# 2-FET_Control.net
KiCad netlist of a schematic drawn in Altium Designer
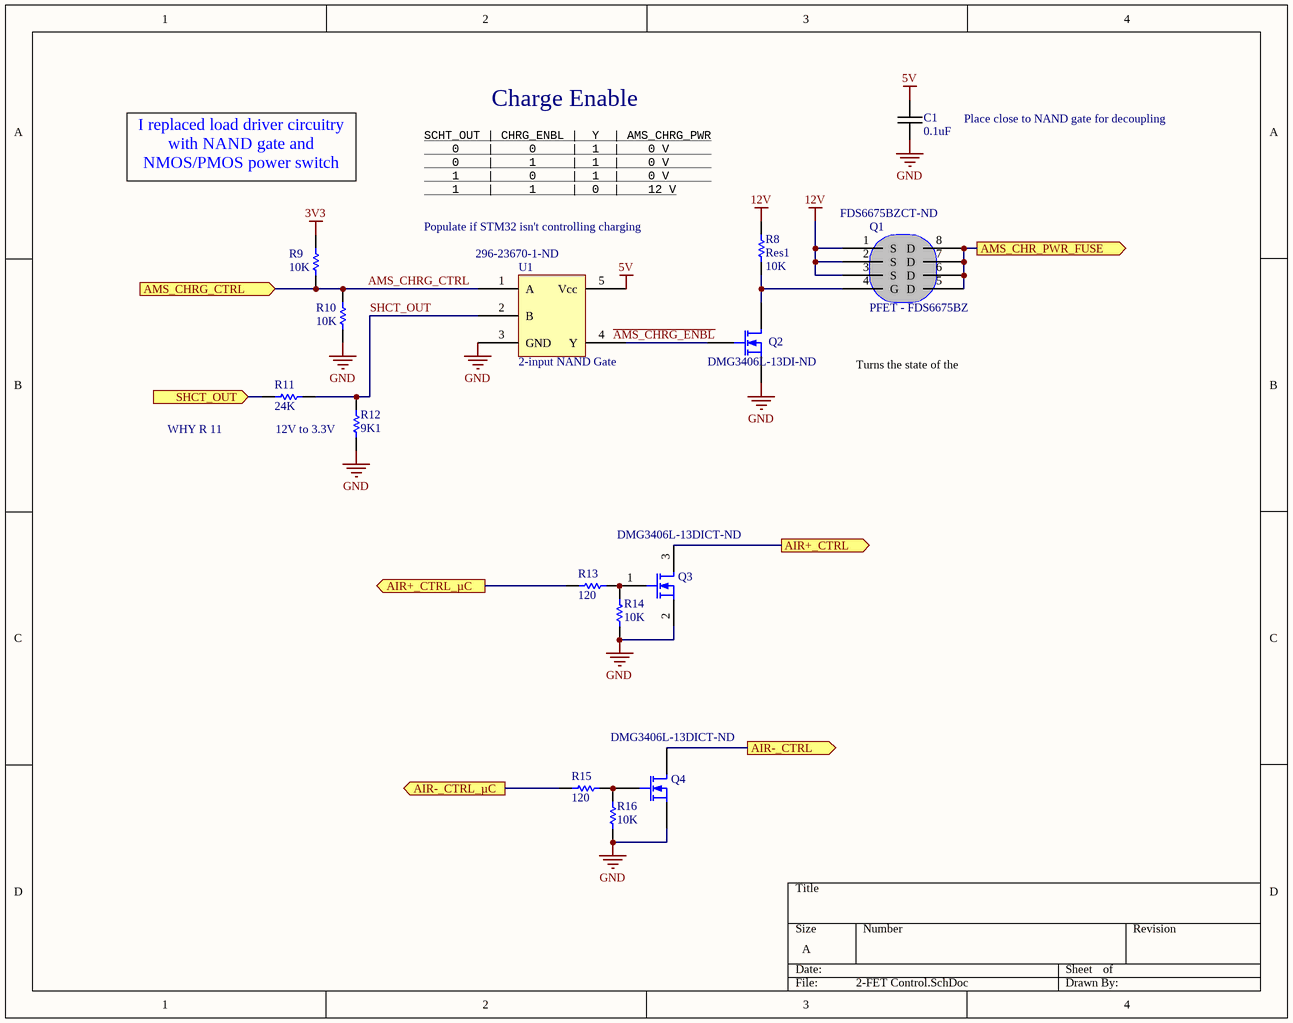
[diagram p0: 2-FET Control.SchDoc]

(export (version "E")
  (design (tool "Eeschema 10.0.6"))
  (components
    (comp (ref "C1")
      (value "0.1uF")
      (footprint "1608[0603]")
      (description "CAP CER 0.1UF 50V X7R 0603")
      (fields
        (field (name "MANUFACTURER") "Kemet")
        (field (name "MANUFACTURER PART NUMBER") "C0603C104K5RACAUTO")
      )
      (libsource (lib "vh_altium_library") (part "0805C-100nF-25V-X7R-MUR"))
    )
    (comp (ref "Q1")
      (value "PFET - FDS6675BZ")
      (footprint "SOIC127P600X175-8N")
      (description "MOSFET P-CH 8-SOIC")
      (fields
        (field (name "MANUFACTURER") "Fairchild/ON Semiconductor")
        (field (name "MANUFACTURER PART NUMBER") "FDS6675BZ")
        (field (name "SUPPLIER PART NUMBER 1") "FDS6675BZCT-ND")
      )
      (libsource (lib "Latching_Reset_Library") (part "MOSFET"))
    )
    (comp (ref "Q2")
      (value "~")
      (footprint "SOT-23_N")
      (description "N-Channel MOSFET")
      (fields
        (field (name "MANUFACTURER") "Infineon Technologies")
        (field (name "MANUFACTURER PART NUMBER") "IPD075N03L G")
        (field (name "SUPPLIER PART NUMBER 1") "DMG3406L-13DI-ND")
        (field (name "PUBLISHER") "Altium Limited")
      )
      (libsource (lib "") (part "MOSFET-N_1"))
    )
    (comp (ref "Q3")
      (value "~")
      (footprint "SOT-23_N")
      (description "N-Channel MOSFET")
      (fields
        (field (name "MANUFACTURER") "Infineon Technologies")
        (field (name "MANUFACTURER PART NUMBER") "IPD075N03L G")
        (field (name "SUPPLIER PART NUMBER 1") "DMG3406L-13DICT-ND")
        (field (name "PUBLISHER") "Altium Limited")
      )
      (libsource (lib "Miscellaneous Devices") (part "MOSFET-N"))
    )
    (comp (ref "Q4")
      (value "~")
      (footprint "SOT-23_N")
      (description "N-Channel MOSFET")
      (fields
        (field (name "MANUFACTURER") "Infineon Technologies")
        (field (name "MANUFACTURER PART NUMBER") "IPD075N03L G")
        (field (name "SUPPLIER PART NUMBER 1") "DMG3406L-13DICT-ND")
        (field (name "PUBLISHER") "Altium Limited")
      )
      (libsource (lib "") (part "MOSFET-N_1"))
    )
    (comp (ref "R8")
      (value "Res1")
      (footprint "1608[0603]")
      (description "RES SMD 10K OHM 5% 1/4W 0603")
      (fields
        (field (name "ALTIUM_VALUE") "10K")
        (field (name "MANUFACTURER") "Rohm Semiconductor")
        (field (name "MANUFACTURER PART NUMBER") "ESR03EZPJ103")
        (field (name "PUBLISHER") "Altium Limited")
      )
      (libsource (lib "Miscellaneous Devices") (part "Res1"))
    )
    (comp (ref "R9")
      (value "10K")
      (footprint "RESC0603(1608)_L")
      (description "0603 (1608 Metric) Chip Resistor")
      (libsource (lib "Altium Content Vault") (part "CMP-1591-00001-1"))
    )
    (comp (ref "R10")
      (value "10K")
      (footprint "RESC0603(1608)_L")
      (description "0603 (1608 Metric) Chip Resistor")
      (libsource (lib "Altium Content Vault") (part "CMP-1591-00001-1"))
    )
    (comp (ref "R11")
      (value "24K")
      (footprint "RESC0603(1608)_N")
      (description "24K 0.1W 5% 0603 (1608 Metric)  SMD")
      (fields (field (name "TOLERANCE") "5 %") (field (name "POWER") "0.1 W"))
      (libsource (lib "Altium Content Vault") (part "RES"))
    )
    (comp (ref "R12")
      (value "9K1")
      (footprint "RESC0603(1608)_M")
      (description "9K1 0.1W 5% 0603 (1608 Metric)  SMD")
      (fields (field (name "POWER") "0.1 W") (field (name "TOLERANCE") "5 %"))
      (libsource (lib "Altium Content Vault") (part "RES"))
    )
    (comp (ref "R13")
      (value "120")
      (footprint "1608[0603]")
      (description "Resistor")
      (fields
        (field (name "MANUFACTURER") "Panasonic Electronic Components")
        (field (name "MANUFACTURER PART NUMBER") "ERJ-3EKF60R4V")
        (field (name "PUBLISHER") "Altium Limited")
      )
      (libsource (lib "Miscellaneous Devices") (part "Res1"))
    )
    (comp (ref "R14")
      (value "10K")
      (footprint "1608[0603]")
      (description "Resistor")
      (fields
        (field (name "MANUFACTURER") "Rohm Semiconductor")
        (field (name "MANUFACTURER PART NUMBER") "ESR03EZPJ103")
        (field (name "PUBLISHER") "Altium Limited")
      )
      (libsource (lib "Miscellaneous Devices") (part "Res1"))
    )
    (comp (ref "R15")
      (value "120")
      (footprint "1608[0603]")
      (description "Resistor")
      (fields
        (field (name "MANUFACTURER") "Panasonic Electronic Components")
        (field (name "MANUFACTURER PART NUMBER") "ERJ-3EKF60R4V")
        (field (name "PUBLISHER") "Altium Limited")
      )
      (libsource (lib "Miscellaneous Devices") (part "Res1"))
    )
    (comp (ref "R16")
      (value "10K")
      (footprint "1608[0603]")
      (description "Resistor")
      (fields
        (field (name "MANUFACTURER") "Rohm Semiconductor")
        (field (name "MANUFACTURER PART NUMBER") "ESR03EZPJ103")
        (field (name "PUBLISHER") "Altium Limited")
      )
      (libsource (lib "Miscellaneous Devices") (part "Res1"))
    )
    (comp (ref "U1")
      (value "2-input NAND Gate")
      (footprint "SOT23-6_M")
      (description "IC GATE NAND 1CH 2-INP SC-70-5")
      (fields
        (field (name "MANUFACTURER") "Texas Instruments")
        (field (name "MANUFACTURER PART NUMBER") "SN74AHC1G00QDCKRQ1")
        (field (name "SUPPLIER PART NUMBER 1") "296-23670-1-ND")
      )
      (libsource (lib "FE Schem Lib") (part "NC7SZ08"))
    )
  )
  (nets
    (net (code "1") (name "/AIR+_CTRL") (class "Default")
      (node (ref "Q3") (pin "3") (pinfunction "D_3") (pintype "passive"))
    )
    (net (code "2") (name "/AIR+_CTRL_µC") (class "Default")
      (node (ref "R13") (pin "1") (pinfunction "1_1") (pintype "passive"))
    )
    (net (code "3") (name "/AIR-_CTRL") (class "Default")
      (node (ref "Q4") (pin "3") (pinfunction "D_3") (pintype "passive"))
    )
    (net (code "4") (name "/AIR-_CTRL_µC") (class "Default")
      (node (ref "R15") (pin "1") (pinfunction "1_1") (pintype "passive"))
    )
    (net (code "5") (name "/AMS_CHRG_CTRL") (class "Default")
      (node (ref "R10") (pin "2") (pinfunction "2_2") (pintype "passive"))
      (node (ref "R9") (pin "1") (pinfunction "1_1") (pintype "passive"))
      (node (ref "U1") (pin "1") (pinfunction "A_1") (pintype "passive"))
    )
    (net (code "6") (name "/AMS_CHR_PWR_FUSE") (class "Default")
      (node (ref "Q1") (pin "5") (pinfunction "D_5") (pintype "passive"))
      (node (ref "Q1") (pin "6") (pinfunction "D_6") (pintype "passive"))
      (node (ref "Q1") (pin "7") (pinfunction "D_7") (pintype "passive"))
      (node (ref "Q1") (pin "8") (pinfunction "D_8") (pintype "passive"))
    )
    (net (code "7") (name "/SHCT_OUT") (class "Default")
      (node (ref "R11") (pin "1") (pinfunction "1_1") (pintype "passive"))
      (node (ref "R11") (pin "2") (pinfunction "2_2") (pintype "passive"))
      (node (ref "R12") (pin "2") (pinfunction "2_2") (pintype "passive"))
      (node (ref "U1") (pin "2") (pinfunction "B_2") (pintype "passive"))
    )
    (net (code "9") (name "3V3") (class "Default")
      (node (ref "R9") (pin "2") (pinfunction "2_2") (pintype "passive"))
    )
    (net (code "10") (name "5V") (class "Default")
      (node (ref "C1") (pin "1") (pintype "passive"))
      (node (ref "U1") (pin "5") (pinfunction "Vcc_5") (pintype "passive"))
    )
    (net (code "11") (name "12V") (class "Default")
      (node (ref "Q1") (pin "1") (pinfunction "S_1") (pintype "passive"))
      (node (ref "Q1") (pin "2") (pinfunction "S_2") (pintype "passive"))
      (node (ref "Q1") (pin "3") (pinfunction "S_3") (pintype "passive"))
      (node (ref "R8") (pin "2") (pinfunction "2_2") (pintype "passive"))
    )
    (net (code "12") (name "GND") (class "Default")
      (node (ref "C1") (pin "2") (pintype "passive"))
      (node (ref "Q2") (pin "2") (pinfunction "S_2") (pintype "passive"))
      (node (ref "Q3") (pin "2") (pinfunction "S_2") (pintype "passive"))
      (node (ref "Q4") (pin "2") (pinfunction "S_2") (pintype "passive"))
      (node (ref "R10") (pin "1") (pinfunction "1_1") (pintype "passive"))
      (node (ref "R12") (pin "1") (pinfunction "1_1") (pintype "passive"))
      (node (ref "R14") (pin "1") (pinfunction "1_1") (pintype "passive"))
      (node (ref "R16") (pin "1") (pinfunction "1_1") (pintype "passive"))
      (node (ref "U1") (pin "3") (pinfunction "GND_3") (pintype "passive"))
    )
    (net (code "13") (name "Net-(Q1-G)") (class "Default")
      (node (ref "Q1") (pin "4") (pinfunction "G_4") (pintype "passive"))
      (node (ref "Q2") (pin "3") (pinfunction "D_3") (pintype "passive"))
      (node (ref "R8") (pin "1") (pinfunction "1_1") (pintype "passive"))
    )
    (net (code "14") (name "Net-(Q2-G)") (class "Default")
      (node (ref "Q2") (pin "1") (pinfunction "G_1") (pintype "passive"))
      (node (ref "U1") (pin "4") (pinfunction "Y_4") (pintype "passive"))
    )
    (net (code "15") (name "Net-(Q3-G)") (class "Default")
      (node (ref "Q3") (pin "1") (pinfunction "G_1") (pintype "passive"))
      (node (ref "R13") (pin "2") (pinfunction "2_2") (pintype "passive"))
      (node (ref "R14") (pin "2") (pinfunction "2_2") (pintype "passive"))
    )
    (net (code "16") (name "Net-(Q4-G)") (class "Default")
      (node (ref "Q4") (pin "1") (pinfunction "G_1") (pintype "passive"))
      (node (ref "R15") (pin "2") (pinfunction "2_2") (pintype "passive"))
      (node (ref "R16") (pin "2") (pinfunction "2_2") (pintype "passive"))
    )
  )
)
